# 1712.net
KiCad netlist of a schematic drawn in Altium Designer
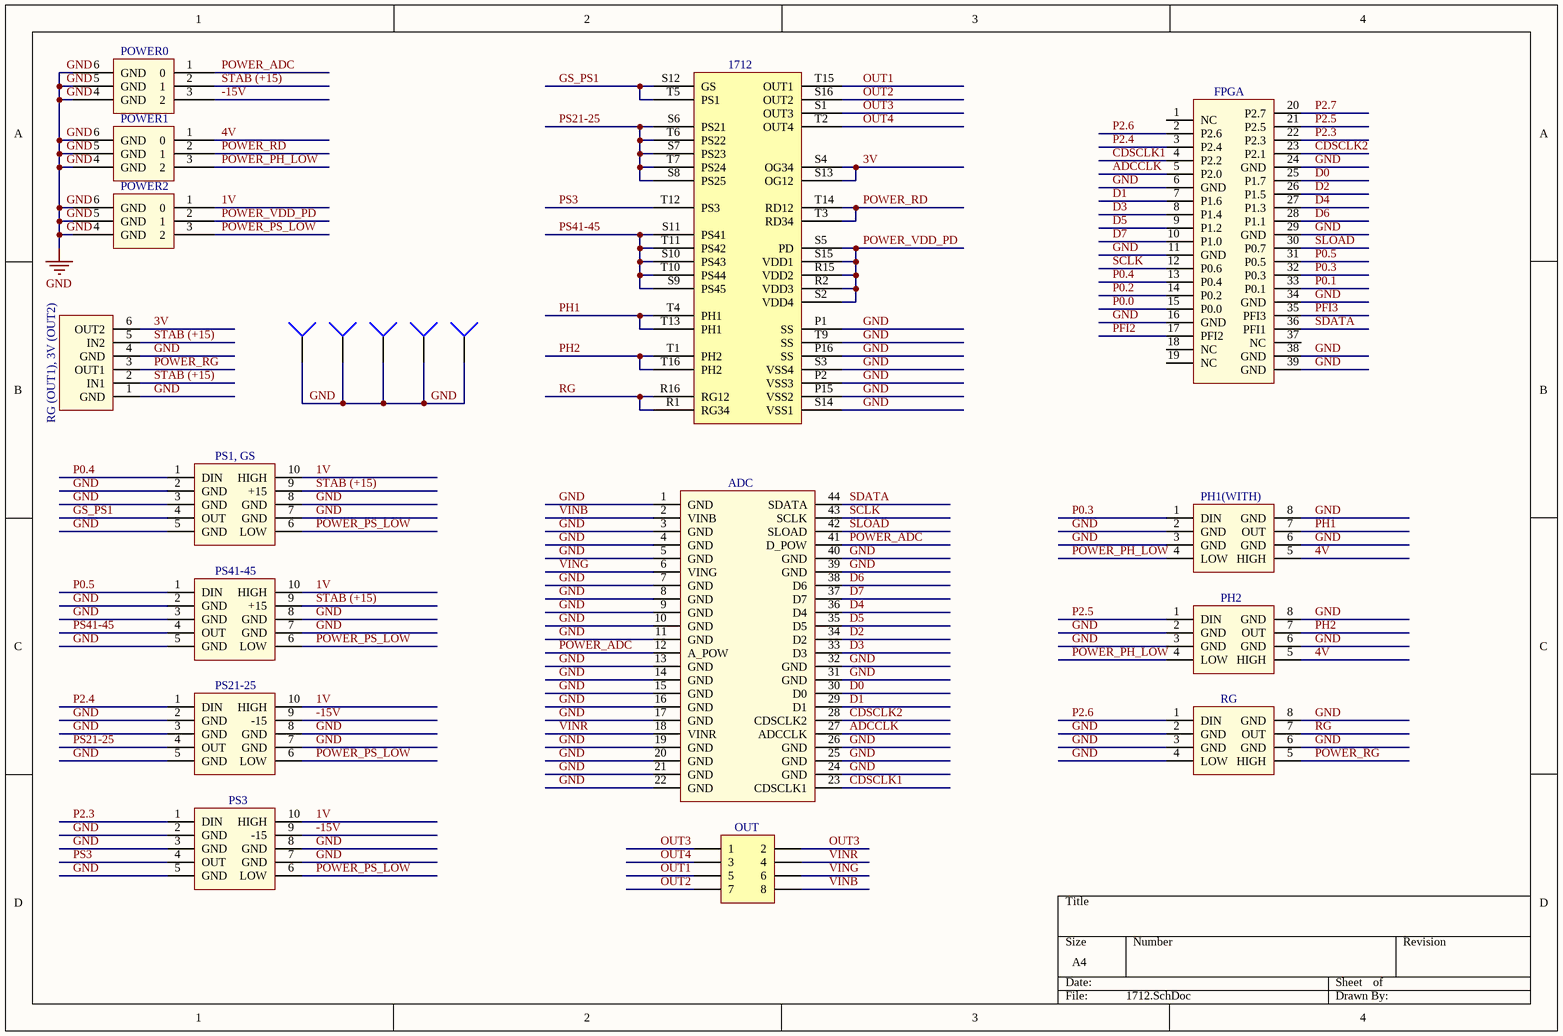
[diagram p0: 1712.SchDoc]

(export (version "E")
  (design (tool "Eeschema 10.0.6"))
  (components
    (comp (ref "1712")
      (value "Б1712А-3")
      (footprint "Dzr_place")
      (libsource (lib "Dzr_SchLib") (part "Б1712А-3"))
    )
    (comp (ref "ADC")
      (value "MEZON_ADC")
      (footprint "MEZON_ADC")
      (libsource (lib "Schlib") (part "MEZON_ADC"))
    )
    (comp (ref "FPGA")
      (value "CHEAP_CON_37_FEMALE")
      (footprint "CHEAP_CONN_FEMALE")
      (libsource (lib "Schlib") (part "CHEAP_CON_37_FEMALE"))
    )
    (comp (ref "J1")
      (value "Socket")
      (footprint "PIN1")
      (fields (field (name "PUBLISHER") "Altium Limited"))
      (libsource (lib "Miscellaneous Connectors") (part "Socket"))
    )
    (comp (ref "J2")
      (value "Socket")
      (footprint "PIN1")
      (fields (field (name "PUBLISHER") "Altium Limited"))
      (libsource (lib "Miscellaneous Connectors") (part "Socket"))
    )
    (comp (ref "J3")
      (value "Socket")
      (footprint "PIN1")
      (fields (field (name "PUBLISHER") "Altium Limited"))
      (libsource (lib "Miscellaneous Connectors") (part "Socket"))
    )
    (comp (ref "J4")
      (value "Socket")
      (footprint "PIN1")
      (fields (field (name "PUBLISHER") "Altium Limited"))
      (libsource (lib "Miscellaneous Connectors") (part "Socket"))
    )
    (comp (ref "J5")
      (value "Socket")
      (footprint "PIN1")
      (fields (field (name "PUBLISHER") "Altium Limited"))
      (libsource (lib "Miscellaneous Connectors") (part "Socket"))
    )
    (comp (ref "OUT")
      (value "Header 4X2")
      (footprint "HDR2X4")
      (description "Header, 4-Pin, Dual row")
      (fields (field (name "PUBLISHER") "Altium Limited"))
      (libsource (lib "Miscellaneous Connectors") (part "Header 4X2"))
    )
    (comp (ref "PH1(WITH)")
      (value "MEZON_H")
      (footprint "MEZON_H")
      (libsource (lib "Schlib") (part "MEZON_H"))
    )
    (comp (ref "PH2") (value "MEZON_H") (footprint "MEZON_H") (libsource (lib "Schlib") (part "MEZON_H")))
    (comp (ref "POWER0") (value "POWER") (footprint "POWER") (libsource (lib "Schlib") (part "POWER")))
    (comp (ref "POWER1") (value "POWER") (footprint "POWER") (libsource (lib "Schlib") (part "POWER")))
    (comp (ref "POWER2") (value "POWER") (footprint "POWER") (libsource (lib "Schlib") (part "POWER")))
    (comp (ref "PS1, GS")
      (value "MEZON_V+15")
      (footprint "MEZON_V")
      (libsource (lib "Schlib") (part "MEZON_V_+15"))
    )
    (comp (ref "PS3") (value "MEZON_V") (footprint "MEZON_V") (libsource (lib "Schlib") (part "MEZON_V")))
    (comp (ref "PS21-25") (value "MEZON_V") (footprint "MEZON_V") (libsource (lib "Schlib") (part "MEZON_V")))
    (comp (ref "PS41-45")
      (value "MEZON_V+15")
      (footprint "MEZON_V")
      (libsource (lib "Schlib") (part "MEZON_V_+15"))
    )
    (comp (ref "RG") (value "MEZON_H") (footprint "MEZON_H") (libsource (lib "Schlib") (part "MEZON_H")))
    (comp (ref "RG (OUT1), 3V (OUT2)")
      (value "MEZ_POWER")
      (footprint "MEZON_POWER_NEW")
      (libsource (lib "Schlib") (part "MEZON_POWER_NEW"))
    )
  )
  (nets
    (net (code "1") (name "/-15V") (class "Default")
      (node (ref "POWER0") (pin "3") (pinfunction "2_3") (pintype "passive"))
      (node (ref "PS21-25") (pin "9") (pinfunction "-15_9") (pintype "passive"))
      (node (ref "PS3") (pin "9") (pinfunction "-15_9") (pintype "passive"))
    )
    (net (code "2") (name "/1V") (class "Default")
      (node (ref "POWER2") (pin "1") (pinfunction "0_1") (pintype "passive"))
      (node (ref "PS1, GS") (pin "10") (pinfunction "HIGH_10") (pintype "passive"))
      (node (ref "PS21-25") (pin "10") (pinfunction "HIGH_10") (pintype "passive"))
      (node (ref "PS3") (pin "10") (pinfunction "HIGH_10") (pintype "passive"))
      (node (ref "PS41-45") (pin "10") (pinfunction "HIGH_10") (pintype "passive"))
    )
    (net (code "3") (name "/3V") (class "Default")
      (node (ref "1712") (pin "S13") (pinfunction "OG12_S13") (pintype "passive"))
      (node (ref "1712") (pin "S4") (pinfunction "OG34_S4") (pintype "passive"))
      (node (ref "RG (OUT1), 3V (OUT2)") (pin "6") (pinfunction "OUT2_6") (pintype "passive"))
    )
    (net (code "4") (name "/4V") (class "Default")
      (node (ref "PH1(WITH)") (pin "5") (pinfunction "HIGH_5") (pintype "passive"))
      (node (ref "PH2") (pin "5") (pinfunction "HIGH_5") (pintype "passive"))
      (node (ref "POWER1") (pin "1") (pinfunction "0_1") (pintype "passive"))
    )
    (net (code "5") (name "/ADCCLK") (class "Default")
      (node (ref "ADC") (pin "27") (pinfunction "ADCCLK_27") (pintype "passive"))
      (node (ref "FPGA") (pin "5") (pinfunction "P2.0_5") (pintype "passive"))
    )
    (net (code "6") (name "/CDSCLK1") (class "Default")
      (node (ref "ADC") (pin "23") (pinfunction "CDSCLK1_23") (pintype "passive"))
      (node (ref "FPGA") (pin "4") (pinfunction "P2.2_4") (pintype "passive"))
    )
    (net (code "7") (name "/CDSCLK2") (class "Default")
      (node (ref "ADC") (pin "28") (pinfunction "CDSCLK2_28") (pintype "passive"))
      (node (ref "FPGA") (pin "23") (pinfunction "P2.1_23") (pintype "passive"))
    )
    (net (code "8") (name "/D0") (class "Default")
      (node (ref "ADC") (pin "30") (pinfunction "D0_30") (pintype "passive"))
      (node (ref "FPGA") (pin "25") (pinfunction "P1.7_25") (pintype "passive"))
    )
    (net (code "9") (name "/D1") (class "Default")
      (node (ref "ADC") (pin "29") (pinfunction "D1_29") (pintype "passive"))
      (node (ref "FPGA") (pin "7") (pinfunction "P1.6_7") (pintype "passive"))
    )
    (net (code "10") (name "/D2") (class "Default")
      (node (ref "ADC") (pin "34") (pinfunction "D2_34") (pintype "passive"))
      (node (ref "FPGA") (pin "26") (pinfunction "P1.5_26") (pintype "passive"))
    )
    (net (code "11") (name "/D3") (class "Default")
      (node (ref "ADC") (pin "33") (pinfunction "D3_33") (pintype "passive"))
      (node (ref "FPGA") (pin "8") (pinfunction "P1.4_8") (pintype "passive"))
    )
    (net (code "12") (name "/D4") (class "Default")
      (node (ref "ADC") (pin "36") (pinfunction "D4_36") (pintype "passive"))
      (node (ref "FPGA") (pin "27") (pinfunction "P1.3_27") (pintype "passive"))
    )
    (net (code "13") (name "/D5") (class "Default")
      (node (ref "ADC") (pin "35") (pinfunction "D5_35") (pintype "passive"))
      (node (ref "FPGA") (pin "9") (pinfunction "P1.2_9") (pintype "passive"))
    )
    (net (code "14") (name "/D6") (class "Default")
      (node (ref "ADC") (pin "38") (pinfunction "D6_38") (pintype "passive"))
      (node (ref "FPGA") (pin "28") (pinfunction "P1.1_28") (pintype "passive"))
    )
    (net (code "15") (name "/D7") (class "Default")
      (node (ref "ADC") (pin "37") (pinfunction "D7_37") (pintype "passive"))
      (node (ref "FPGA") (pin "10") (pinfunction "P1.0_10") (pintype "passive"))
    )
    (net (code "16") (name "/GS_PS1") (class "Default")
      (node (ref "1712") (pin "S12") (pinfunction "GS_S12") (pintype "passive"))
      (node (ref "1712") (pin "T5") (pinfunction "PS1_T5") (pintype "passive"))
      (node (ref "PS1, GS") (pin "4") (pinfunction "OUT_4") (pintype "passive"))
    )
    (net (code "17") (name "/OUT1") (class "Default")
      (node (ref "1712") (pin "T15") (pinfunction "OUT1_T15") (pintype "passive"))
      (node (ref "OUT") (pin "5") (pinfunction "5_5") (pintype "passive"))
    )
    (net (code "18") (name "/OUT2") (class "Default")
      (node (ref "1712") (pin "S16") (pinfunction "OUT2_S16") (pintype "passive"))
      (node (ref "OUT") (pin "7") (pinfunction "7_7") (pintype "passive"))
    )
    (net (code "19") (name "/OUT3") (class "Default")
      (node (ref "1712") (pin "S1") (pinfunction "OUT3_S1") (pintype "passive"))
      (node (ref "OUT") (pin "1") (pinfunction "1_1") (pintype "passive"))
      (node (ref "OUT") (pin "2") (pinfunction "2_2") (pintype "passive"))
    )
    (net (code "20") (name "/OUT4") (class "Default")
      (node (ref "1712") (pin "T2") (pinfunction "OUT4_T2") (pintype "passive"))
      (node (ref "OUT") (pin "3") (pinfunction "3_3") (pintype "passive"))
    )
    (net (code "21") (name "/P0.0") (class "Default")
      (node (ref "FPGA") (pin "15") (pinfunction "P0.0_15") (pintype "passive"))
    )
    (net (code "22") (name "/P0.1") (class "Default")
      (node (ref "FPGA") (pin "33") (pinfunction "P0.1_33") (pintype "passive"))
    )
    (net (code "23") (name "/P0.2") (class "Default")
      (node (ref "FPGA") (pin "14") (pinfunction "P0.2_14") (pintype "passive"))
    )
    (net (code "24") (name "/P0.3") (class "Default")
      (node (ref "FPGA") (pin "32") (pinfunction "P0.3_32") (pintype "passive"))
      (node (ref "PH1(WITH)") (pin "1") (pinfunction "DIN_1") (pintype "passive"))
    )
    (net (code "25") (name "/P0.4") (class "Default")
      (node (ref "FPGA") (pin "13") (pinfunction "P0.4_13") (pintype "passive"))
      (node (ref "PS1, GS") (pin "1") (pinfunction "DIN_1") (pintype "passive"))
    )
    (net (code "26") (name "/P0.5") (class "Default")
      (node (ref "FPGA") (pin "31") (pinfunction "P0.5_31") (pintype "passive"))
      (node (ref "PS41-45") (pin "1") (pinfunction "DIN_1") (pintype "passive"))
    )
    (net (code "27") (name "/P2.3") (class "Default")
      (node (ref "FPGA") (pin "22") (pinfunction "P2.3_22") (pintype "passive"))
      (node (ref "PS3") (pin "1") (pinfunction "DIN_1") (pintype "passive"))
    )
    (net (code "28") (name "/P2.4") (class "Default")
      (node (ref "FPGA") (pin "3") (pinfunction "P2.4_3") (pintype "passive"))
      (node (ref "PS21-25") (pin "1") (pinfunction "DIN_1") (pintype "passive"))
    )
    (net (code "29") (name "/P2.5") (class "Default")
      (node (ref "FPGA") (pin "21") (pinfunction "P2.5_21") (pintype "passive"))
      (node (ref "PH2") (pin "1") (pinfunction "DIN_1") (pintype "passive"))
    )
    (net (code "30") (name "/P2.6") (class "Default")
      (node (ref "FPGA") (pin "2") (pinfunction "P2.6_2") (pintype "passive"))
      (node (ref "RG") (pin "1") (pinfunction "DIN_1") (pintype "passive"))
    )
    (net (code "31") (name "/P2.7") (class "Default")
      (node (ref "FPGA") (pin "20") (pinfunction "P2.7_20") (pintype "passive"))
    )
    (net (code "32") (name "/PFI2") (class "Default")
      (node (ref "FPGA") (pin "17") (pinfunction "PFI2_17") (pintype "passive"))
    )
    (net (code "33") (name "/PFI3") (class "Default")
      (node (ref "FPGA") (pin "35") (pinfunction "PFI3_35") (pintype "passive"))
    )
    (net (code "34") (name "/PH1") (class "Default")
      (node (ref "1712") (pin "T13") (pinfunction "PH1_T13") (pintype "passive"))
      (node (ref "1712") (pin "T4") (pinfunction "PH1_T4") (pintype "passive"))
      (node (ref "PH1(WITH)") (pin "7") (pinfunction "OUT_7") (pintype "passive"))
    )
    (net (code "35") (name "/PH2") (class "Default")
      (node (ref "1712") (pin "T1") (pinfunction "PH2_T1") (pintype "passive"))
      (node (ref "1712") (pin "T16") (pinfunction "PH2_T16") (pintype "passive"))
      (node (ref "PH2") (pin "7") (pinfunction "OUT_7") (pintype "passive"))
    )
    (net (code "36") (name "/POWER_ADC") (class "Default")
      (node (ref "ADC") (pin "12") (pinfunction "A_POW_12") (pintype "passive"))
      (node (ref "ADC") (pin "41") (pinfunction "D_POW_41") (pintype "passive"))
      (node (ref "POWER0") (pin "1") (pinfunction "0_1") (pintype "passive"))
    )
    (net (code "37") (name "/POWER_PH_LOW") (class "Default")
      (node (ref "PH1(WITH)") (pin "4") (pinfunction "LOW_4") (pintype "passive"))
      (node (ref "PH2") (pin "4") (pinfunction "LOW_4") (pintype "passive"))
      (node (ref "POWER1") (pin "3") (pinfunction "2_3") (pintype "passive"))
    )
    (net (code "38") (name "/POWER_PS_LOW") (class "Default")
      (node (ref "POWER2") (pin "3") (pinfunction "2_3") (pintype "passive"))
      (node (ref "PS1, GS") (pin "6") (pinfunction "LOW_6") (pintype "passive"))
      (node (ref "PS21-25") (pin "6") (pinfunction "LOW_6") (pintype "passive"))
      (node (ref "PS3") (pin "6") (pinfunction "LOW_6") (pintype "passive"))
      (node (ref "PS41-45") (pin "6") (pinfunction "LOW_6") (pintype "passive"))
    )
    (net (code "39") (name "/POWER_RD") (class "Default")
      (node (ref "1712") (pin "T14") (pinfunction "RD12_T14") (pintype "passive"))
      (node (ref "1712") (pin "T3") (pinfunction "RD34_T3") (pintype "passive"))
      (node (ref "POWER1") (pin "2") (pinfunction "1_2") (pintype "passive"))
    )
    (net (code "40") (name "/POWER_RG") (class "Default")
      (node (ref "RG") (pin "5") (pinfunction "HIGH_5") (pintype "passive"))
      (node (ref "RG (OUT1), 3V (OUT2)") (pin "3") (pinfunction "OUT1_3") (pintype "passive"))
    )
    (net (code "41") (name "/POWER_VDD_PD") (class "Default")
      (node (ref "1712") (pin "R15") (pinfunction "VDD2_R15") (pintype "passive"))
      (node (ref "1712") (pin "R2") (pinfunction "VDD3_R2") (pintype "passive"))
      (node (ref "1712") (pin "S15") (pinfunction "VDD1_S15") (pintype "passive"))
      (node (ref "1712") (pin "S2") (pinfunction "VDD4_S2") (pintype "passive"))
      (node (ref "1712") (pin "S5") (pinfunction "PD_S5") (pintype "passive"))
      (node (ref "POWER2") (pin "2") (pinfunction "1_2") (pintype "passive"))
    )
    (net (code "42") (name "/PS3") (class "Default")
      (node (ref "1712") (pin "T12") (pinfunction "PS3_T12") (pintype "passive"))
      (node (ref "PS3") (pin "4") (pinfunction "OUT_4") (pintype "passive"))
    )
    (net (code "43") (name "/PS21-25") (class "Default")
      (node (ref "1712") (pin "S6") (pinfunction "PS21_S6") (pintype "passive"))
      (node (ref "1712") (pin "S7") (pinfunction "PS23_S7") (pintype "passive"))
      (node (ref "1712") (pin "S8") (pinfunction "PS25_S8") (pintype "passive"))
      (node (ref "1712") (pin "T6") (pinfunction "PS22_T6") (pintype "passive"))
      (node (ref "1712") (pin "T7") (pinfunction "PS24_T7") (pintype "passive"))
      (node (ref "PS21-25") (pin "4") (pinfunction "OUT_4") (pintype "passive"))
    )
    (net (code "44") (name "/PS41-45") (class "Default")
      (node (ref "1712") (pin "S10") (pinfunction "PS43_S10") (pintype "passive"))
      (node (ref "1712") (pin "S11") (pinfunction "PS41_S11") (pintype "passive"))
      (node (ref "1712") (pin "S9") (pinfunction "PS45_S9") (pintype "passive"))
      (node (ref "1712") (pin "T10") (pinfunction "PS44_T10") (pintype "passive"))
      (node (ref "1712") (pin "T11") (pinfunction "PS42_T11") (pintype "passive"))
      (node (ref "PS41-45") (pin "4") (pinfunction "OUT_4") (pintype "passive"))
    )
    (net (code "45") (name "/RG") (class "Default")
      (node (ref "1712") (pin "R1") (pinfunction "RG34_R1") (pintype "passive"))
      (node (ref "1712") (pin "R16") (pinfunction "RG12_R16") (pintype "passive"))
      (node (ref "RG") (pin "7") (pinfunction "OUT_7") (pintype "passive"))
    )
    (net (code "46") (name "/SCLK") (class "Default")
      (node (ref "ADC") (pin "43") (pinfunction "SCLK_43") (pintype "passive"))
      (node (ref "FPGA") (pin "12") (pinfunction "P0.6_12") (pintype "passive"))
    )
    (net (code "47") (name "/SDATA") (class "Default")
      (node (ref "ADC") (pin "44") (pinfunction "SDATA_44") (pintype "passive"))
      (node (ref "FPGA") (pin "36") (pinfunction "PFI1_36") (pintype "passive"))
    )
    (net (code "48") (name "/SLOAD") (class "Default")
      (node (ref "ADC") (pin "42") (pinfunction "SLOAD_42") (pintype "passive"))
      (node (ref "FPGA") (pin "30") (pinfunction "P0.7_30") (pintype "passive"))
    )
    (net (code "49") (name "/STAB (+15)") (class "Default")
      (node (ref "POWER0") (pin "2") (pinfunction "1_2") (pintype "passive"))
      (node (ref "PS1, GS") (pin "9") (pinfunction "+15_9") (pintype "passive"))
      (node (ref "PS41-45") (pin "9") (pinfunction "+15_9") (pintype "passive"))
      (node (ref "RG (OUT1), 3V (OUT2)") (pin "2") (pinfunction "IN1_2") (pintype "passive"))
      (node (ref "RG (OUT1), 3V (OUT2)") (pin "5") (pinfunction "IN2_5") (pintype "passive"))
    )
    (net (code "50") (name "/VINB") (class "Default")
      (node (ref "ADC") (pin "2") (pinfunction "VINB_2") (pintype "passive"))
      (node (ref "OUT") (pin "8") (pinfunction "8_8") (pintype "passive"))
    )
    (net (code "51") (name "/VING") (class "Default")
      (node (ref "ADC") (pin "6") (pinfunction "VING_6") (pintype "passive"))
      (node (ref "OUT") (pin "6") (pinfunction "6_6") (pintype "passive"))
    )
    (net (code "52") (name "/VINR") (class "Default")
      (node (ref "ADC") (pin "18") (pinfunction "VINR_18") (pintype "passive"))
      (node (ref "OUT") (pin "4") (pinfunction "4_4") (pintype "passive"))
    )
    (net (code "53") (name "GND") (class "Default")
      (node (ref "1712") (pin "P1") (pinfunction "SS_P1") (pintype "passive"))
      (node (ref "1712") (pin "P15") (pinfunction "VSS2_P15") (pintype "passive"))
      (node (ref "1712") (pin "P16") (pinfunction "SS_P16") (pintype "passive"))
      (node (ref "1712") (pin "P2") (pinfunction "VSS3_P2") (pintype "passive"))
      (node (ref "1712") (pin "S14") (pinfunction "VSS1_S14") (pintype "passive"))
      (node (ref "1712") (pin "S3") (pinfunction "VSS4_S3") (pintype "passive"))
      (node (ref "1712") (pin "T9") (pinfunction "SS_T9") (pintype "passive"))
      (node (ref "ADC") (pin "1") (pinfunction "GND_1") (pintype "passive"))
      (node (ref "ADC") (pin "10") (pinfunction "GND_10") (pintype "passive"))
      (node (ref "ADC") (pin "11") (pinfunction "GND_11") (pintype "passive"))
      (node (ref "ADC") (pin "13") (pinfunction "GND_13") (pintype "passive"))
      (node (ref "ADC") (pin "14") (pinfunction "GND_14") (pintype "passive"))
      (node (ref "ADC") (pin "15") (pinfunction "GND_15") (pintype "passive"))
      (node (ref "ADC") (pin "16") (pinfunction "GND_16") (pintype "passive"))
      (node (ref "ADC") (pin "17") (pinfunction "GND_17") (pintype "passive"))
      (node (ref "ADC") (pin "19") (pinfunction "GND_19") (pintype "passive"))
      (node (ref "ADC") (pin "20") (pinfunction "GND_20") (pintype "passive"))
      (node (ref "ADC") (pin "21") (pinfunction "GND_21") (pintype "passive"))
      (node (ref "ADC") (pin "22") (pinfunction "GND_22") (pintype "passive"))
      (node (ref "ADC") (pin "24") (pinfunction "GND_24") (pintype "passive"))
      (node (ref "ADC") (pin "25") (pinfunction "GND_25") (pintype "passive"))
      (node (ref "ADC") (pin "26") (pinfunction "GND_26") (pintype "passive"))
      (node (ref "ADC") (pin "3") (pinfunction "GND_3") (pintype "passive"))
      (node (ref "ADC") (pin "31") (pinfunction "GND_31") (pintype "passive"))
      (node (ref "ADC") (pin "32") (pinfunction "GND_32") (pintype "passive"))
      (node (ref "ADC") (pin "39") (pinfunction "GND_39") (pintype "passive"))
      (node (ref "ADC") (pin "4") (pinfunction "GND_4") (pintype "passive"))
      (node (ref "ADC") (pin "40") (pinfunction "GND_40") (pintype "passive"))
      (node (ref "ADC") (pin "5") (pinfunction "GND_5") (pintype "passive"))
      (node (ref "ADC") (pin "7") (pinfunction "GND_7") (pintype "passive"))
      (node (ref "ADC") (pin "8") (pinfunction "GND_8") (pintype "passive"))
      (node (ref "ADC") (pin "9") (pinfunction "GND_9") (pintype "passive"))
      (node (ref "FPGA") (pin "11") (pinfunction "GND_11") (pintype "passive"))
      (node (ref "FPGA") (pin "16") (pinfunction "GND_16") (pintype "passive"))
      (node (ref "FPGA") (pin "24") (pinfunction "GND_24") (pintype "passive"))
      (node (ref "FPGA") (pin "29") (pinfunction "GND_29") (pintype "passive"))
      (node (ref "FPGA") (pin "34") (pinfunction "GND_34") (pintype "passive"))
      (node (ref "FPGA") (pin "38") (pinfunction "GND_38") (pintype "passive"))
      (node (ref "FPGA") (pin "39") (pinfunction "GND_39") (pintype "passive"))
      (node (ref "FPGA") (pin "6") (pinfunction "GND_6") (pintype "passive"))
      (node (ref "J1") (pin "1") (pinfunction "1_1") (pintype "passive"))
      (node (ref "J2") (pin "1") (pinfunction "1_1") (pintype "passive"))
      (node (ref "J3") (pin "1") (pinfunction "1_1") (pintype "passive"))
      (node (ref "J4") (pin "1") (pinfunction "1_1") (pintype "passive"))
      (node (ref "J5") (pin "1") (pinfunction "1_1") (pintype "passive"))
      (node (ref "PH1(WITH)") (pin "2") (pinfunction "GND_2") (pintype "passive"))
      (node (ref "PH1(WITH)") (pin "3") (pinfunction "GND_3") (pintype "passive"))
      (node (ref "PH1(WITH)") (pin "6") (pinfunction "GND_6") (pintype "passive"))
      (node (ref "PH1(WITH)") (pin "8") (pinfunction "GND_8") (pintype "passive"))
      (node (ref "PH2") (pin "2") (pinfunction "GND_2") (pintype "passive"))
      (node (ref "PH2") (pin "3") (pinfunction "GND_3") (pintype "passive"))
      (node (ref "PH2") (pin "6") (pinfunction "GND_6") (pintype "passive"))
      (node (ref "PH2") (pin "8") (pinfunction "GND_8") (pintype "passive"))
      (node (ref "POWER0") (pin "4") (pinfunction "GND_4") (pintype "passive"))
      (node (ref "POWER0") (pin "5") (pinfunction "GND_5") (pintype "passive"))
      (node (ref "POWER0") (pin "6") (pinfunction "GND_6") (pintype "passive"))
      (node (ref "POWER1") (pin "4") (pinfunction "GND_4") (pintype "passive"))
      (node (ref "POWER1") (pin "5") (pinfunction "GND_5") (pintype "passive"))
      (node (ref "POWER1") (pin "6") (pinfunction "GND_6") (pintype "passive"))
      (node (ref "POWER2") (pin "4") (pinfunction "GND_4") (pintype "passive"))
      (node (ref "POWER2") (pin "5") (pinfunction "GND_5") (pintype "passive"))
      (node (ref "POWER2") (pin "6") (pinfunction "GND_6") (pintype "passive"))
      (node (ref "PS1, GS") (pin "2") (pinfunction "GND_2") (pintype "passive"))
      (node (ref "PS1, GS") (pin "3") (pinfunction "GND_3") (pintype "passive"))
      (node (ref "PS1, GS") (pin "5") (pinfunction "GND_5") (pintype "passive"))
      (node (ref "PS1, GS") (pin "7") (pinfunction "GND_7") (pintype "passive"))
      (node (ref "PS1, GS") (pin "8") (pinfunction "GND_8") (pintype "passive"))
      (node (ref "PS21-25") (pin "2") (pinfunction "GND_2") (pintype "passive"))
      (node (ref "PS21-25") (pin "3") (pinfunction "GND_3") (pintype "passive"))
      (node (ref "PS21-25") (pin "5") (pinfunction "GND_5") (pintype "passive"))
      (node (ref "PS21-25") (pin "7") (pinfunction "GND_7") (pintype "passive"))
      (node (ref "PS21-25") (pin "8") (pinfunction "GND_8") (pintype "passive"))
      (node (ref "PS3") (pin "2") (pinfunction "GND_2") (pintype "passive"))
      (node (ref "PS3") (pin "3") (pinfunction "GND_3") (pintype "passive"))
      (node (ref "PS3") (pin "5") (pinfunction "GND_5") (pintype "passive"))
      (node (ref "PS3") (pin "7") (pinfunction "GND_7") (pintype "passive"))
      (node (ref "PS3") (pin "8") (pinfunction "GND_8") (pintype "passive"))
      (node (ref "PS41-45") (pin "2") (pinfunction "GND_2") (pintype "passive"))
      (node (ref "PS41-45") (pin "3") (pinfunction "GND_3") (pintype "passive"))
      (node (ref "PS41-45") (pin "5") (pinfunction "GND_5") (pintype "passive"))
      (node (ref "PS41-45") (pin "7") (pinfunction "GND_7") (pintype "passive"))
      (node (ref "PS41-45") (pin "8") (pinfunction "GND_8") (pintype "passive"))
      (node (ref "RG") (pin "2") (pinfunction "GND_2") (pintype "passive"))
      (node (ref "RG") (pin "3") (pinfunction "GND_3") (pintype "passive"))
      (node (ref "RG") (pin "4") (pinfunction "LOW_4") (pintype "passive"))
      (node (ref "RG") (pin "6") (pinfunction "GND_6") (pintype "passive"))
      (node (ref "RG") (pin "8") (pinfunction "GND_8") (pintype "passive"))
      (node (ref "RG (OUT1), 3V (OUT2)") (pin "1") (pinfunction "GND_1") (pintype "passive"))
      (node (ref "RG (OUT1), 3V (OUT2)") (pin "4") (pinfunction "GND_4") (pintype "passive"))
    )
    (net (code "54") (name "unconnected-(FPGA-NC-Pad1)") (class "Default")
      (node (ref "FPGA") (pin "1") (pinfunction "NC_1") (pintype "passive"))
    )
    (net (code "55") (name "unconnected-(FPGA-NC-Pad18)") (class "Default")
      (node (ref "FPGA") (pin "18") (pinfunction "NC_18") (pintype "passive"))
    )
    (net (code "56") (name "unconnected-(FPGA-NC-Pad19)") (class "Default")
      (node (ref "FPGA") (pin "19") (pinfunction "NC_19") (pintype "passive"))
    )
    (net (code "57") (name "unconnected-(FPGA-NC-Pad37)") (class "Default")
      (node (ref "FPGA") (pin "37") (pinfunction "NC_37") (pintype "passive"))
    )
  )
)
